# Sensorboard.net
KiCad netlist of a schematic drawn in Altium Designer
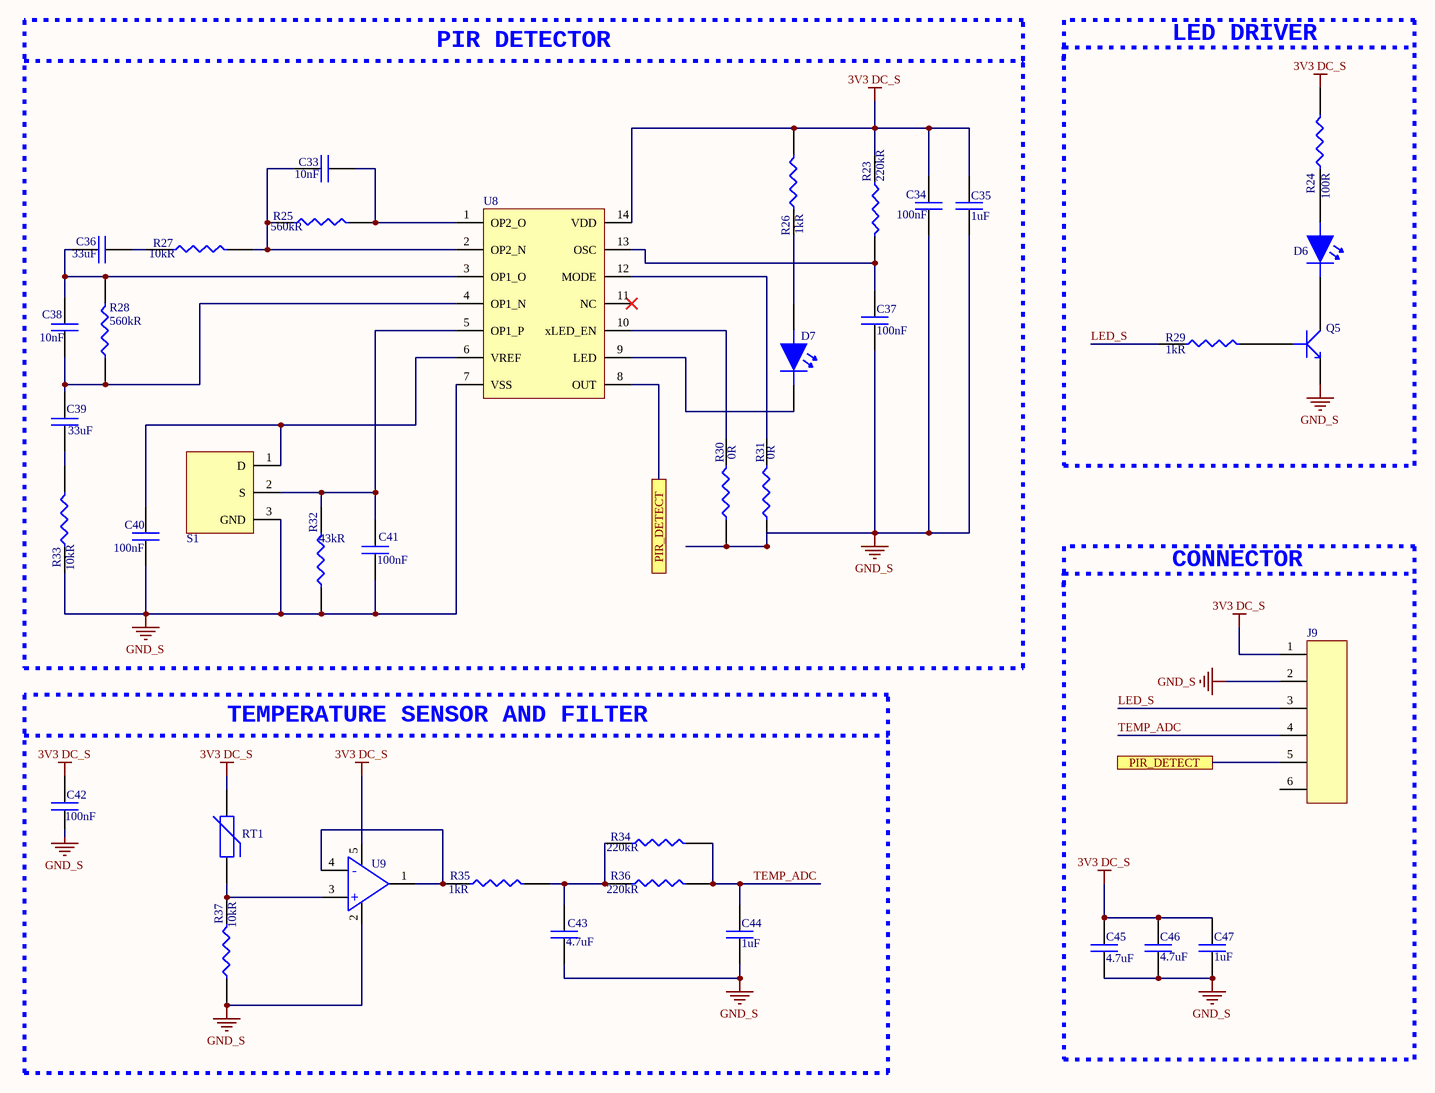
[diagram p0: Sensorboard.SchDoc]

(export (version "E")
  (design (tool "Eeschema 10.0.6"))
  (components
    (comp (ref "C33")
      (value "0603B103K160CT")
      (footprint "CAP_0603")
      (description "Ceramic Capacitor, 10 nF, ± 10%, 0603")
      (fields
        (field (name "MANUFACTURER") "Walsin Technologies")
        (field (name "CAPACITANCE") "10nF")
        (field (name "DESIGNED BY") "berkay")
      )
      (libsource (lib "FirstProject_Library") (part "CAP CER 10nF 0603"))
    )
    (comp (ref "C34")
      (value "CL21B104KBCNNNC")
      (footprint "CAP_0805")
      (description "Ceramic Capacitor, 0.1 uF, 50 V, ï¿½ 10%, X7R, 0805 [2012 Metric]")
      (fields
        (field (name "MANUFACTURER") "Samsung")
        (field (name "TOLERANCE") "10%")
        (field (name "CAPACITANCE") "100nF")
        (field (name "DESIGNED BY") "berkay")
      )
      (libsource (lib "FirstProject_Library") (part "CAP CER 100nF 0805"))
    )
    (comp (ref "C35")
      (value "CL21B105KBFNNNE")
      (footprint "CAP_0805")
      (description "Ceramic Capacitor, 1 uF, 50 V, ï¿½ 10%, X7R, 0805 [2012 Metric]")
      (fields
        (field (name "MANUFACTURER") "Samsung")
        (field (name "TOLERANCE") "10%")
        (field (name "CAPACITANCE") "1uF")
        (field (name "DESIGNED BY") "berkay")
      )
      (libsource (lib "FirstProject_Library") (part "CAP CER 1uF 0805"))
    )
    (comp (ref "C36")
      (value "C3216X5R1E336M160AC")
      (footprint "CAP_1206")
      (description "Ceramic Capacitor, 33 uF, 25 V, ± 20%, X5R, 1206 [3216 Metric]")
      (fields
        (field (name "MANUFACTURER") "TDK")
        (field (name "CAPACITANCE") "33uF")
        (field (name "DESIGNED BY") "berkay")
      )
      (libsource (lib "FirstProject_Library") (part "CAP CER 33uF 1206"))
    )
    (comp (ref "C37")
      (value "CL21B104KBCNNNC")
      (footprint "CAP_0805")
      (description "Ceramic Capacitor, 0.1 uF, 50 V, ï¿½ 10%, X7R, 0805 [2012 Metric]")
      (fields
        (field (name "MANUFACTURER") "Samsung")
        (field (name "TOLERANCE") "10%")
        (field (name "CAPACITANCE") "100nF")
        (field (name "DESIGNED BY") "berkay")
      )
      (libsource (lib "FirstProject_Library") (part "CAP CER 100nF 0805"))
    )
    (comp (ref "C38")
      (value "0603B103K160CT")
      (footprint "CAP_0603")
      (description "Ceramic Capacitor, 10 nF, ± 10%, 0603")
      (fields
        (field (name "MANUFACTURER") "Walsin Technologies")
        (field (name "CAPACITANCE") "10nF")
        (field (name "DESIGNED BY") "berkay")
      )
      (libsource (lib "FirstProject_Library") (part "CAP CER 10nF 0603"))
    )
    (comp (ref "C39")
      (value "C3216X5R1E336M160AC")
      (footprint "CAP_1206")
      (description "Ceramic Capacitor, 33 uF, 25 V, ± 20%, X5R, 1206 [3216 Metric]")
      (fields
        (field (name "MANUFACTURER") "TDK")
        (field (name "CAPACITANCE") "33uF")
        (field (name "DESIGNED BY") "berkay")
      )
      (libsource (lib "FirstProject_Library") (part "CAP CER 33uF 1206"))
    )
    (comp (ref "C40")
      (value "CL21B104KBCNNNC")
      (footprint "CAP_0805")
      (description "Ceramic Capacitor, 0.1 uF, 50 V, ï¿½ 10%, X7R, 0805 [2012 Metric]")
      (fields
        (field (name "MANUFACTURER") "Samsung")
        (field (name "TOLERANCE") "10%")
        (field (name "CAPACITANCE") "100nF")
        (field (name "DESIGNED BY") "berkay")
      )
      (libsource (lib "FirstProject_Library") (part "CAP CER 100nF 0805"))
    )
    (comp (ref "C41")
      (value "CL21B104KBCNNNC")
      (footprint "CAP_0805")
      (description "Ceramic Capacitor, 0.1 uF, 50 V, ï¿½ 10%, X7R, 0805 [2012 Metric]")
      (fields
        (field (name "MANUFACTURER") "Samsung")
        (field (name "TOLERANCE") "10%")
        (field (name "CAPACITANCE") "100nF")
        (field (name "DESIGNED BY") "berkay")
      )
      (libsource (lib "FirstProject_Library") (part "CAP CER 100nF 0805"))
    )
    (comp (ref "C42")
      (value "CL21B104KBCNNNC")
      (footprint "CAP_0805")
      (description "Ceramic Capacitor, 0.1 uF, 50 V, ï¿½ 10%, X7R, 0805 [2012 Metric]")
      (fields
        (field (name "MANUFACTURER") "Samsung")
        (field (name "TOLERANCE") "10%")
        (field (name "CAPACITANCE") "100nF")
        (field (name "DESIGNED BY") "berkay")
      )
      (libsource (lib "FirstProject_Library") (part "CAP CER 100nF 0805"))
    )
    (comp (ref "C43")
      (value "CL21A475KAQNNNE")
      (footprint "CAP_0805")
      (description "Ceramic Capacitor, 4.7 uF, 25 V, ± 10%, X5R, 0805 [2012 Metric]")
      (fields
        (field (name "MANUFACTURER") "Samsung")
        (field (name "TOLERANCE") "10%")
        (field (name "CAPACITANCE") "4.7uF")
        (field (name "DESIGNED BY") "berkay")
      )
      (libsource (lib "FirstProject_Library") (part "CAP CER 4.7uF 0805"))
    )
    (comp (ref "C44")
      (value "CL21B105KBFNNNE")
      (footprint "CAP_0805")
      (description "Ceramic Capacitor, 1 uF, 50 V, ï¿½ 10%, X7R, 0805 [2012 Metric]")
      (fields
        (field (name "MANUFACTURER") "Samsung")
        (field (name "TOLERANCE") "10%")
        (field (name "CAPACITANCE") "1uF")
        (field (name "DESIGNED BY") "berkay")
      )
      (libsource (lib "FirstProject_Library") (part "CAP CER 1uF 0805"))
    )
    (comp (ref "C45")
      (value "CL21A475KAQNNNE")
      (footprint "CAP_0805")
      (description "Ceramic Capacitor, 4.7 uF, 25 V, ± 10%, X5R, 0805 [2012 Metric]")
      (fields
        (field (name "MANUFACTURER") "Samsung")
        (field (name "TOLERANCE") "10%")
        (field (name "CAPACITANCE") "4.7uF")
        (field (name "DESIGNED BY") "berkay")
      )
      (libsource (lib "FirstProject_Library") (part "CAP CER 4.7uF 0805"))
    )
    (comp (ref "C46")
      (value "CL21A475KAQNNNE")
      (footprint "CAP_0805")
      (description "Ceramic Capacitor, 4.7 uF, 25 V, ± 10%, X5R, 0805 [2012 Metric]")
      (fields
        (field (name "MANUFACTURER") "Samsung")
        (field (name "TOLERANCE") "10%")
        (field (name "CAPACITANCE") "4.7uF")
        (field (name "DESIGNED BY") "berkay")
      )
      (libsource (lib "FirstProject_Library") (part "CAP CER 4.7uF 0805"))
    )
    (comp (ref "C47")
      (value "CL21B105KBFNNNE")
      (footprint "CAP_0805")
      (description "Ceramic Capacitor, 1 uF, 50 V, ï¿½ 10%, X7R, 0805 [2012 Metric]")
      (fields
        (field (name "MANUFACTURER") "Samsung")
        (field (name "TOLERANCE") "10%")
        (field (name "CAPACITANCE") "1uF")
        (field (name "DESIGNED BY") "berkay")
      )
      (libsource (lib "FirstProject_Library") (part "CAP CER 1uF 0805"))
    )
    (comp (ref "D6")
      (value "150080RS75000")
      (footprint "LED_RED_0805")
      (description "LED Uni-Color Red 630nm 2-Pin Chip 0805(2012Metric) T/R")
      (fields (field (name "MANUFACTURER") "Wurth Electronics") (field (name "DESIGNED BY") "berkay"))
      (libsource (lib "FirstProject_Library") (part "LED RED 0805"))
    )
    (comp (ref "D7")
      (value "150080GS75000")
      (footprint "LED_GREEN_0805")
      (description "WURTH ELEKTRONIK - 150080GS75000 - LED, Green, SMD, 0805, 30 mA, 3.2 V, 520 nm")
      (fields (field (name "MANUFACTURER") "Wurth Electronics") (field (name "DESIGNED BY") "berkay"))
      (libsource (lib "FirstProject_Library") (part "LED GREEN 0805"))
    )
    (comp (ref "J9")
      (value "64800611622")
      (footprint "64800611622")
      (description "WR-WTB Wire-to-Board Connectors 1.50 mm")
      (fields (field (name "MANUFACTURER") "Wurth Electronics"))
      (libsource (lib "FirstProject_Library") (part "64800611622_conn_6pin"))
    )
    (comp (ref "Q5")
      (value "MMBT3904-7-F")
      (footprint "SOT23F")
      (description "Transistor General Purpose BJT NPN 40 Volt 0.2A Automotive 3-Pin SOT-23")
      (fields (field (name "MANUFACTURER") "Diodes Zetex") (field (name "DESIGNED BY") "berkay"))
      (libsource (lib "FirstProject_Library") (part "MMBT3904-7-F"))
    )
    (comp (ref "R23")
      (value "RC0603JR-07220KL")
      (footprint "RES_0603")
      (description "SMD Chip Resistor, 220 kOhm, ï¿½ 5%, 100 mW, 0603 [1608 Metric], Thick Film, General Purpose")
      (fields
        (field (name "MANUFACTURER") "Yageo")
        (field (name "RESISTANCE") "220kR")
        (field (name "DESIGNED BY") "berkay")
      )
      (libsource (lib "FirstProject_Library") (part "RES 220K OHM 0603"))
    )
    (comp (ref "R24")
      (value "RC0603FR-07100RL")
      (footprint "RES_0603")
      (description "SMD Chip Resistor, 100 Ohm, ï¿½ 1%, 100 mW, 0603 [1608 Metric], Thick Film, General Purpose")
      (fields
        (field (name "MANUFACTURER") "Yageo")
        (field (name "TOLERANCE") "1%")
        (field (name "RESISTANCE") "100R")
        (field (name "DESIGNED BY") "berkay")
      )
      (libsource (lib "FirstProject_Library") (part "RES 100 OHM 0603"))
    )
    (comp (ref "R25")
      (value "RC0603JR-07560KL")
      (footprint "RES_0603")
      (description "SMD Chip Resistor, 560 kOhm, ï¿½ 5%, 100 mW, 0603 [1608 Metric], Thick Film, General Purpose")
      (fields
        (field (name "MANUFACTURER") "Yageo")
        (field (name "TOLERANCE") "5%")
        (field (name "RESISTANCE") "560kR")
        (field (name "DESIGNED BY") "berkay")
      )
      (libsource (lib "FirstProject_Library") (part "RES 560k OHM 0603"))
    )
    (comp (ref "R26")
      (value "RC0603FR-071KL")
      (footprint "RES_0603")
      (description "SMD Chip Resistor, 1 kOhm, ï¿½ 1%, 100 mW, 0603 [1608 Metric], Thick Film, General Purpose")
      (fields
        (field (name "MANUFACTURER") "Yageo")
        (field (name "TOLERANCE") "1%")
        (field (name "RESISTANCE") "1kR")
        (field (name "DESIGNED BY") "berkay")
      )
      (libsource (lib "FirstProject_Library") (part "RES 1K OHM 0603"))
    )
    (comp (ref "R27")
      (value "RC0603FR-0710KL")
      (footprint "RES_0603")
      (description "SMD Chip Resistor, 10 kOhm, ï¿½ 1%, 100 mW, 0603 [1608 Metric], Thick Film, General Purpose")
      (fields
        (field (name "MANUFACTURER") "Yageo")
        (field (name "TOLERANCE") "1%")
        (field (name "RESISTANCE") "10kR")
        (field (name "DESIGNED BY") "berkay")
      )
      (libsource (lib "FirstProject_Library") (part "RES 10K OHM 0603"))
    )
    (comp (ref "R28")
      (value "RC0603JR-07560KL")
      (footprint "RES_0603")
      (description "SMD Chip Resistor, 560 kOhm, ï¿½ 5%, 100 mW, 0603 [1608 Metric], Thick Film, General Purpose")
      (fields
        (field (name "MANUFACTURER") "Yageo")
        (field (name "TOLERANCE") "5%")
        (field (name "RESISTANCE") "560kR")
        (field (name "DESIGNED BY") "berkay")
      )
      (libsource (lib "FirstProject_Library") (part "RES 560k OHM 0603"))
    )
    (comp (ref "R29")
      (value "RC0603FR-071KL")
      (footprint "RES_0603")
      (description "SMD Chip Resistor, 1 kOhm, ï¿½ 1%, 100 mW, 0603 [1608 Metric], Thick Film, General Purpose")
      (fields
        (field (name "MANUFACTURER") "Yageo")
        (field (name "TOLERANCE") "1%")
        (field (name "RESISTANCE") "1kR")
        (field (name "DESIGNED BY") "berkay")
      )
      (libsource (lib "FirstProject_Library") (part "RES 1K OHM 0603"))
    )
    (comp (ref "R30")
      (value "RC0603JR-070RL")
      (footprint "RES_0603")
      (description "GENERAL PURPOSE CHIP RESISTOR Metal Glaze/thick Film, 0.1W, 0ohm, Surface Mount, 0603")
      (fields
        (field (name "MANUFACTURER") "Yageo")
        (field (name "TOLERANCE") "1%")
        (field (name "RESISTANCE") "0R")
        (field (name "DESIGNED BY") "berkay")
      )
      (libsource (lib "FirstProject_Library") (part "RES 0 OHM 0603"))
    )
    (comp (ref "R31")
      (value "RC0603JR-070RL")
      (footprint "RES_0603")
      (description "GENERAL PURPOSE CHIP RESISTOR Metal Glaze/thick Film, 0.1W, 0ohm, Surface Mount, 0603")
      (fields
        (field (name "MANUFACTURER") "Yageo")
        (field (name "TOLERANCE") "1%")
        (field (name "RESISTANCE") "0R")
        (field (name "DESIGNED BY") "berkay")
      )
      (libsource (lib "FirstProject_Library") (part "RES 0 OHM 0603"))
    )
    (comp (ref "R32")
      (value "RC0603FR-0743KL")
      (footprint "RES_0603")
      (description "SMD Chip Resistor, 43 kOhm, ï¿½ 1%, 100 mW, 0603 [1608 Metric], Thick Film, General Purpose")
      (fields
        (field (name "MANUFACTURER") "Yageo")
        (field (name "RESISTANCE") "43kR")
        (field (name "DESIGNED BY") "berkay")
      )
      (libsource (lib "FirstProject_Library") (part "RES 43K OHM 0603"))
    )
    (comp (ref "R33")
      (value "RC0603FR-0710KL")
      (footprint "RES_0603")
      (description "SMD Chip Resistor, 10 kOhm, ï¿½ 1%, 100 mW, 0603 [1608 Metric], Thick Film, General Purpose")
      (fields
        (field (name "MANUFACTURER") "Yageo")
        (field (name "TOLERANCE") "1%")
        (field (name "RESISTANCE") "10kR")
        (field (name "DESIGNED BY") "berkay")
      )
      (libsource (lib "FirstProject_Library") (part "RES 10K OHM 0603"))
    )
    (comp (ref "R34")
      (value "RC0603JR-07220KL")
      (footprint "RES_0603")
      (description "SMD Chip Resistor, 220 kOhm, ï¿½ 5%, 100 mW, 0603 [1608 Metric], Thick Film, General Purpose")
      (fields
        (field (name "MANUFACTURER") "Yageo")
        (field (name "RESISTANCE") "220kR")
        (field (name "DESIGNED BY") "berkay")
      )
      (libsource (lib "FirstProject_Library") (part "RES 220K OHM 0603"))
    )
    (comp (ref "R35")
      (value "RC0603FR-071KL")
      (footprint "RES_0603")
      (description "SMD Chip Resistor, 1 kOhm, ï¿½ 1%, 100 mW, 0603 [1608 Metric], Thick Film, General Purpose")
      (fields
        (field (name "MANUFACTURER") "Yageo")
        (field (name "TOLERANCE") "1%")
        (field (name "RESISTANCE") "1kR")
        (field (name "DESIGNED BY") "berkay")
      )
      (libsource (lib "FirstProject_Library") (part "RES 1K OHM 0603"))
    )
    (comp (ref "R36")
      (value "RC0603JR-07220KL")
      (footprint "RES_0603")
      (description "SMD Chip Resistor, 220 kOhm, ï¿½ 5%, 100 mW, 0603 [1608 Metric], Thick Film, General Purpose")
      (fields
        (field (name "MANUFACTURER") "Yageo")
        (field (name "RESISTANCE") "220kR")
        (field (name "DESIGNED BY") "berkay")
      )
      (libsource (lib "FirstProject_Library") (part "RES 220K OHM 0603"))
    )
    (comp (ref "R37")
      (value "RC0603FR-0710KL")
      (footprint "RES_0603")
      (description "SMD Chip Resistor, 10 kOhm, ï¿½ 1%, 100 mW, 0603 [1608 Metric], Thick Film, General Purpose")
      (fields
        (field (name "MANUFACTURER") "Yageo")
        (field (name "TOLERANCE") "1%")
        (field (name "RESISTANCE") "10kR")
        (field (name "DESIGNED BY") "berkay")
      )
      (libsource (lib "FirstProject_Library") (part "RES 10K OHM 0603"))
    )
    (comp (ref "RT1")
      (value "TFPT1206L1002FM")
      (footprint "RES_1206")
      (description "Thermistor PTC 10K Ohm 1% 2-Pin 1206")
      (fields
        (field (name "MANUFACTURER") "Vishay Dale")
        (field (name "TOLERANCE") "1%")
        (field (name "DESIGNED BY") "berkay")
      )
      (libsource (lib "FirstProject_Library") (part "TFPT1206L1002FM"))
    )
    (comp (ref "S1")
      (value "LHI 878/3902")
      (footprint "LHI 878/3902")
      (description "Sensor PIR (Passive Infrared) TO-205AA, TO-5-3 Metal Can")
      (fields (field (name "MANUFACTURER") "Excelitas Technology") (field (name "DESIGNED BY") "berkay"))
      (libsource (lib "FirstProject_Library") (part "LHI 878/3902"))
    )
    (comp (ref "U8")
      (value "NCS36000DRG")
      (footprint "SOIC-14")
      (description "PIR CONTROLLER NCS36000 Series Single 5.75V Passive Infrared Detector Controller (PIR) -SOIC-14")
      (fields (field (name "MANUFACTURER") "ON Semiconductor") (field (name "DESIGNED BY") "berkay"))
      (libsource (lib "FirstProject_Library") (part "NCS36000"))
    )
    (comp (ref "U9")
      (value "OPA314AIDBVR")
      (footprint "SOT23-5")
      (description "Single, 5.5-V, 3-MHz, low noise (4.6-nV/√Hz), RRIO operational amplifier 5-SOT-23 -40 to 125")
      (fields (field (name "MANUFACTURER") "Texas Instruments") (field (name "DESIGNED BY") "berkay"))
      (libsource (lib "FirstProject_Library") (part "OPA314AIDBVR"))
    )
  )
  (nets
    (net (code "1") (name "/LED_S") (class "Default")
      (node (ref "J9") (pin "3") (pinfunction "3_3") (pintype "passive"))
      (node (ref "R29") (pin "1") (pinfunction "1_1") (pintype "passive"))
    )
    (net (code "2") (name "/PIR_DETECT") (class "Default")
      (node (ref "J9") (pin "5") (pinfunction "5_5") (pintype "passive"))
      (node (ref "U8") (pin "8") (pinfunction "OUT_8") (pintype "passive"))
    )
    (net (code "3") (name "/TEMP_ADC") (class "Default")
      (node (ref "C44") (pin "2") (pinfunction "2_2") (pintype "passive"))
      (node (ref "J9") (pin "4") (pinfunction "4_4") (pintype "passive"))
      (node (ref "R34") (pin "2") (pinfunction "2_2") (pintype "passive"))
      (node (ref "R36") (pin "2") (pinfunction "2_2") (pintype "passive"))
    )
    (net (code "4") (name "3V3 DC_S") (class "Default")
      (node (ref "C34") (pin "2") (pinfunction "2_2") (pintype "passive"))
      (node (ref "C35") (pin "2") (pinfunction "2_2") (pintype "passive"))
      (node (ref "C42") (pin "2") (pinfunction "2_2") (pintype "passive"))
      (node (ref "C45") (pin "2") (pinfunction "2_2") (pintype "passive"))
      (node (ref "C46") (pin "2") (pinfunction "2_2") (pintype "passive"))
      (node (ref "C47") (pin "2") (pinfunction "2_2") (pintype "passive"))
      (node (ref "J9") (pin "1") (pinfunction "1_1") (pintype "passive"))
      (node (ref "R23") (pin "1") (pinfunction "1_1") (pintype "passive"))
      (node (ref "R24") (pin "2") (pinfunction "2_2") (pintype "passive"))
      (node (ref "R26") (pin "2") (pinfunction "2_2") (pintype "passive"))
      (node (ref "RT1") (pin "2") (pinfunction "2_2") (pintype "passive"))
      (node (ref "U8") (pin "14") (pinfunction "VDD_14") (pintype "passive"))
      (node (ref "U9") (pin "5") (pinfunction "5_5") (pintype "passive"))
    )
    (net (code "5") (name "GND_S") (class "Default")
      (node (ref "C34") (pin "1") (pinfunction "1_1") (pintype "passive"))
      (node (ref "C35") (pin "1") (pinfunction "1_1") (pintype "passive"))
      (node (ref "C37") (pin "1") (pinfunction "1_1") (pintype "passive"))
      (node (ref "C40") (pin "1") (pinfunction "1_1") (pintype "passive"))
      (node (ref "C41") (pin "1") (pinfunction "1_1") (pintype "passive"))
      (node (ref "C42") (pin "1") (pinfunction "1_1") (pintype "passive"))
      (node (ref "C43") (pin "2") (pinfunction "2_2") (pintype "passive"))
      (node (ref "C44") (pin "1") (pinfunction "1_1") (pintype "passive"))
      (node (ref "C45") (pin "1") (pinfunction "1_1") (pintype "passive"))
      (node (ref "C46") (pin "1") (pinfunction "1_1") (pintype "passive"))
      (node (ref "C47") (pin "1") (pinfunction "1_1") (pintype "passive"))
      (node (ref "J9") (pin "2") (pinfunction "2_2") (pintype "passive"))
      (node (ref "Q5") (pin "2") (pinfunction "E_2") (pintype "passive"))
      (node (ref "R30") (pin "1") (pinfunction "1_1") (pintype "passive"))
      (node (ref "R31") (pin "1") (pinfunction "1_1") (pintype "passive"))
      (node (ref "R32") (pin "1") (pinfunction "1_1") (pintype "passive"))
      (node (ref "R33") (pin "1") (pinfunction "1_1") (pintype "passive"))
      (node (ref "R37") (pin "1") (pinfunction "1_1") (pintype "passive"))
      (node (ref "S1") (pin "3") (pinfunction "GND_3") (pintype "passive"))
      (node (ref "U8") (pin "7") (pinfunction "VSS_7") (pintype "passive"))
      (node (ref "U9") (pin "2") (pinfunction "2_2") (pintype "passive"))
    )
    (net (code "6") (name "Net-(C36-Pad2)") (class "Default")
      (node (ref "C36") (pin "2") (pinfunction "2_2") (pintype "passive"))
      (node (ref "R27") (pin "1") (pinfunction "1_1") (pintype "passive"))
    )
    (net (code "7") (name "Net-(C39-Pad1)") (class "Default")
      (node (ref "C39") (pin "1") (pinfunction "1_1") (pintype "passive"))
      (node (ref "R33") (pin "2") (pinfunction "2_2") (pintype "passive"))
    )
    (net (code "8") (name "Net-(C43-Pad1)") (class "Default")
      (node (ref "C43") (pin "1") (pinfunction "1_1") (pintype "passive"))
      (node (ref "R34") (pin "1") (pinfunction "1_1") (pintype "passive"))
      (node (ref "R35") (pin "2") (pinfunction "2_2") (pintype "passive"))
      (node (ref "R36") (pin "1") (pinfunction "1_1") (pintype "passive"))
    )
    (net (code "9") (name "Net-(D6-PadA)") (class "Default")
      (node (ref "D6") (pin "A") (pinfunction "A_A") (pintype "passive"))
      (node (ref "R24") (pin "1") (pinfunction "1_1") (pintype "passive"))
    )
    (net (code "10") (name "Net-(D7-PadA)") (class "Default")
      (node (ref "D7") (pin "A") (pinfunction "A_A") (pintype "passive"))
      (node (ref "R26") (pin "1") (pinfunction "1_1") (pintype "passive"))
    )
    (net (code "11") (name "Net-(Q5-B)") (class "Default")
      (node (ref "Q5") (pin "1") (pinfunction "B_1") (pintype "passive"))
      (node (ref "R29") (pin "2") (pinfunction "2_2") (pintype "passive"))
    )
    (net (code "12") (name "Net-(Q5-C)") (class "Default")
      (node (ref "D6") (pin "C") (pinfunction "C_C") (pintype "passive"))
      (node (ref "Q5") (pin "3") (pinfunction "C_3") (pintype "passive"))
    )
    (net (code "13") (name "Net-(S1-D)") (class "Default")
      (node (ref "C40") (pin "2") (pinfunction "2_2") (pintype "passive"))
      (node (ref "S1") (pin "1") (pinfunction "D_1") (pintype "passive"))
      (node (ref "U8") (pin "6") (pinfunction "VREF_6") (pintype "passive"))
    )
    (net (code "14") (name "Net-(S1-S)") (class "Default")
      (node (ref "C41") (pin "2") (pinfunction "2_2") (pintype "passive"))
      (node (ref "R32") (pin "2") (pinfunction "2_2") (pintype "passive"))
      (node (ref "S1") (pin "2") (pinfunction "S_2") (pintype "passive"))
      (node (ref "U8") (pin "5") (pinfunction "OP1_P_5") (pintype "passive"))
    )
    (net (code "15") (name "Net-(U8-LED)") (class "Default")
      (node (ref "D7") (pin "C") (pinfunction "C_C") (pintype "passive"))
      (node (ref "U8") (pin "9") (pinfunction "LED_9") (pintype "passive"))
    )
    (net (code "16") (name "Net-(U8-MODE)") (class "Default")
      (node (ref "R31") (pin "2") (pinfunction "2_2") (pintype "passive"))
      (node (ref "U8") (pin "12") (pinfunction "MODE_12") (pintype "passive"))
    )
    (net (code "17") (name "Net-(U8-OP1_N)") (class "Default")
      (node (ref "C38") (pin "1") (pinfunction "1_1") (pintype "passive"))
      (node (ref "C39") (pin "2") (pinfunction "2_2") (pintype "passive"))
      (node (ref "R28") (pin "1") (pinfunction "1_1") (pintype "passive"))
      (node (ref "U8") (pin "4") (pinfunction "OP1_N_4") (pintype "passive"))
    )
    (net (code "18") (name "Net-(U8-OP1_O)") (class "Default")
      (node (ref "C36") (pin "1") (pinfunction "1_1") (pintype "passive"))
      (node (ref "C38") (pin "2") (pinfunction "2_2") (pintype "passive"))
      (node (ref "R28") (pin "2") (pinfunction "2_2") (pintype "passive"))
      (node (ref "U8") (pin "3") (pinfunction "OP1_O_3") (pintype "passive"))
    )
    (net (code "19") (name "Net-(U8-OP2_N)") (class "Default")
      (node (ref "C33") (pin "1") (pinfunction "1_1") (pintype "passive"))
      (node (ref "R25") (pin "1") (pinfunction "1_1") (pintype "passive"))
      (node (ref "R27") (pin "2") (pinfunction "2_2") (pintype "passive"))
      (node (ref "U8") (pin "2") (pinfunction "OP2_N_2") (pintype "passive"))
    )
    (net (code "20") (name "Net-(U8-OP2_O)") (class "Default")
      (node (ref "C33") (pin "2") (pinfunction "2_2") (pintype "passive"))
      (node (ref "R25") (pin "2") (pinfunction "2_2") (pintype "passive"))
      (node (ref "U8") (pin "1") (pinfunction "OP2_O_1") (pintype "passive"))
    )
    (net (code "21") (name "Net-(U8-OSC)") (class "Default")
      (node (ref "C37") (pin "2") (pinfunction "2_2") (pintype "passive"))
      (node (ref "R23") (pin "2") (pinfunction "2_2") (pintype "passive"))
      (node (ref "U8") (pin "13") (pinfunction "OSC_13") (pintype "passive"))
    )
    (net (code "22") (name "Net-(U8-xLED_EN)") (class "Default")
      (node (ref "R30") (pin "2") (pinfunction "2_2") (pintype "passive"))
      (node (ref "U8") (pin "10") (pinfunction "xLED_EN_10") (pintype "passive"))
    )
    (net (code "23") (name "Net-(U9-+)") (class "Default")
      (node (ref "R37") (pin "2") (pinfunction "2_2") (pintype "passive"))
      (node (ref "RT1") (pin "1") (pinfunction "1_1") (pintype "passive"))
      (node (ref "U9") (pin "3") (pinfunction "+_3") (pintype "passive"))
    )
    (net (code "24") (name "Net-(U9--)") (class "Default")
      (node (ref "R35") (pin "1") (pinfunction "1_1") (pintype "passive"))
      (node (ref "U9") (pin "1") (pinfunction "1_1") (pintype "passive"))
      (node (ref "U9") (pin "4") (pinfunction "-_4") (pintype "passive"))
    )
    (net (code "25") (name "unconnected-(J9-Pad6)") (class "Default")
      (node (ref "J9") (pin "6") (pinfunction "6_6") (pintype "passive"))
    )
    (net (code "26") (name "unconnected-(U8-NC-Pad11)") (class "Default")
      (node (ref "U8") (pin "11") (pinfunction "NC_11") (pintype "passive+no_connect"))
    )
  )
)
